# WCRL_Board_V3.net
KiCad netlist of a schematic drawn in EAGLE
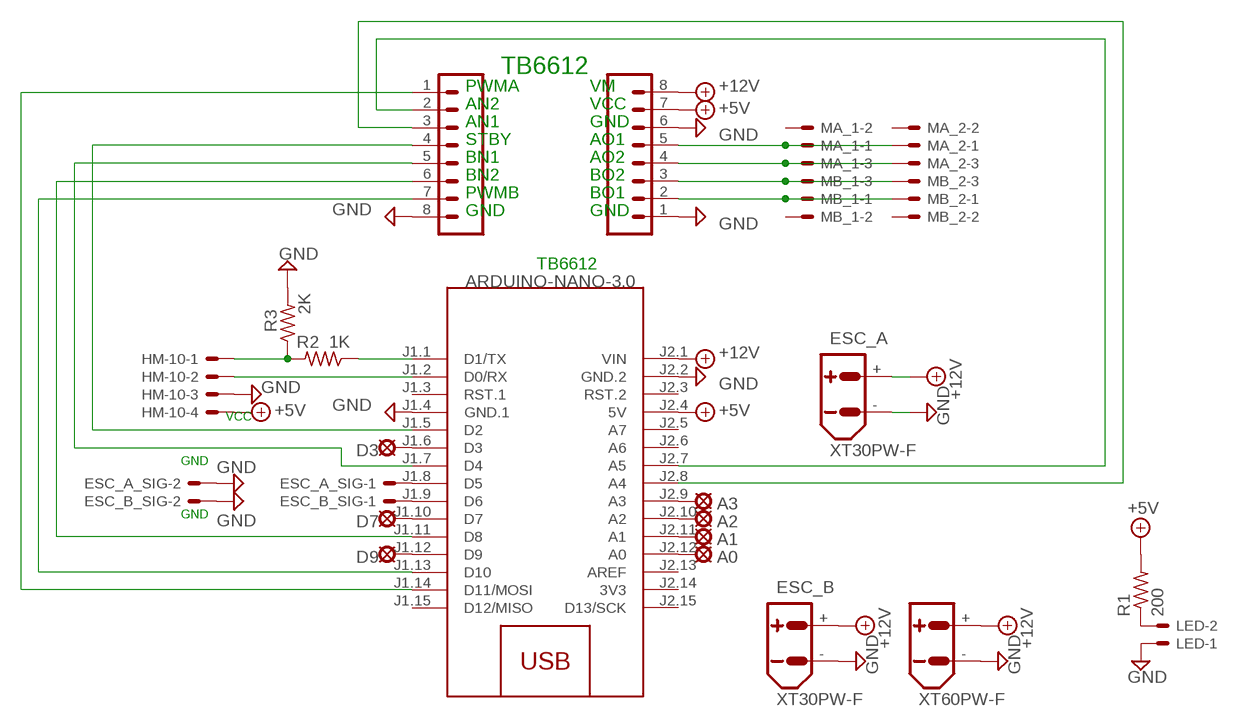
[diagram p0: schematic, sheet 1]

(export (version "E")
  (design (tool "Eeschema 10.0.6"))
  (components
    (comp (ref "A0")
      (value "LSP10")
      (footprint "eagle-import:LSP10")
      (libsource (lib "eagle-import") (part "LSP10"))
    )
    (comp (ref "A1")
      (value "LSP10")
      (footprint "eagle-import:LSP10")
      (libsource (lib "eagle-import") (part "LSP10"))
    )
    (comp (ref "A2")
      (value "LSP10")
      (footprint "eagle-import:LSP10")
      (libsource (lib "eagle-import") (part "LSP10"))
    )
    (comp (ref "A3")
      (value "LSP10")
      (footprint "eagle-import:LSP10")
      (libsource (lib "eagle-import") (part "LSP10"))
    )
    (comp (ref "BATTERY")
      (value "XT60PW-F")
      (footprint "eagle-import:XT60PW-F")
      (libsource (lib "eagle-import") (part "XT60PW-F"))
    )
    (comp (ref "D3")
      (value "LSP10")
      (footprint "eagle-import:LSP10")
      (libsource (lib "eagle-import") (part "LSP10"))
    )
    (comp (ref "D7")
      (value "LSP10")
      (footprint "eagle-import:LSP10")
      (libsource (lib "eagle-import") (part "LSP10"))
    )
    (comp (ref "D9")
      (value "LSP10")
      (footprint "eagle-import:LSP10")
      (libsource (lib "eagle-import") (part "LSP10"))
    )
    (comp (ref "ESC_A")
      (value "XT30PW-F")
      (footprint "eagle-import:XT30PW-F")
      (libsource (lib "eagle-import") (part "XT30PW-F"))
    )
    (comp (ref "ESC_A_SIG")
      (value "JST-XH-02-PIN-LONG-PAD")
      (footprint "eagle-import:JST-XH-02-PACKAGE-LONG-PAD")
      (libsource (lib "eagle-import") (part "JST-XH-02-PIN-LONG-PAD"))
    )
    (comp (ref "ESC_B")
      (value "XT30PW-F")
      (footprint "eagle-import:XT30PW-F")
      (libsource (lib "eagle-import") (part "XT30PW-F"))
    )
    (comp (ref "ESC_B_SIG")
      (value "JST-XH-02-PIN-LONG-PAD")
      (footprint "eagle-import:JST-XH-02-PACKAGE-LONG-PAD")
      (libsource (lib "eagle-import") (part "JST-XH-02-PIN-LONG-PAD"))
    )
    (comp (ref "HM-10")
      (value "JST-XH-04-PIN-LONG-PAD")
      (footprint "eagle-import:JST-XH-04-PACKAGE-LONG-PAD")
      (libsource (lib "eagle-import") (part "JST-XH-04-PIN-LONG-PAD"))
    )
    (comp (ref "J1")
      (value "CONN_08NO_SILK_FEMALE_PTH")
      (footprint "eagle-import:1X08_NO_SILK")
      (libsource (lib "eagle-import") (part "CONN_08NO_SILK_FEMALE_PTH"))
    )
    (comp (ref "J2")
      (value "CONN_08NO_SILK_FEMALE_PTH")
      (footprint "eagle-import:1X08_NO_SILK")
      (libsource (lib "eagle-import") (part "CONN_08NO_SILK_FEMALE_PTH"))
    )
    (comp (ref "LED")
      (value "JST-XH-02-PIN-LONG-PAD")
      (footprint "eagle-import:JST-XH-02-PACKAGE-LONG-PAD")
      (libsource (lib "eagle-import") (part "JST-XH-02-PIN-LONG-PAD"))
    )
    (comp (ref "M1")
      (value "ARDUINO-NANO-3.0")
      (footprint "eagle-import:ARDUINO-NANO-3.0")
      (libsource (lib "eagle-import") (part "ARDUINO-NANO-3.0"))
    )
    (comp (ref "MA_1")
      (value "JST-XH-03-PIN-LONG-PAD")
      (footprint "eagle-import:JST-XH-03-PACKAGE-LONG-PAD")
      (libsource (lib "eagle-import") (part "JST-XH-03-PIN-LONG-PAD"))
    )
    (comp (ref "MA_2")
      (value "JST-XH-03-PIN-LONG-PAD")
      (footprint "eagle-import:JST-XH-03-PACKAGE-LONG-PAD")
      (libsource (lib "eagle-import") (part "JST-XH-03-PIN-LONG-PAD"))
    )
    (comp (ref "MB_1")
      (value "JST-XH-03-PIN-LONG-PAD")
      (footprint "eagle-import:JST-XH-03-PACKAGE-LONG-PAD")
      (libsource (lib "eagle-import") (part "JST-XH-03-PIN-LONG-PAD"))
    )
    (comp (ref "MB_2")
      (value "JST-XH-03-PIN-LONG-PAD")
      (footprint "eagle-import:JST-XH-03-PACKAGE-LONG-PAD")
      (libsource (lib "eagle-import") (part "JST-XH-03-PIN-LONG-PAD"))
    )
    (comp (ref "R1")
      (value "200")
      (footprint "eagle-import:0204_5")
      (libsource (lib "eagle-import") (part "R-US_0204/5"))
    )
    (comp (ref "R2")
      (value "1K")
      (footprint "eagle-import:0204_5")
      (libsource (lib "eagle-import") (part "R-US_0204/5"))
    )
    (comp (ref "R3")
      (value "2K")
      (footprint "eagle-import:0204_5")
      (libsource (lib "eagle-import") (part "R-US_0204/5"))
    )
  )
  (nets
    (net (code "1") (name "+5V") (class "Default")
      (node (ref "HM-10") (pin "4") (pinfunction "S_4") (pintype "passive"))
      (node (ref "J1") (pin "7") (pinfunction "7_7") (pintype "passive"))
      (node (ref "M1") (pin "J2.4") (pinfunction "5V_J2.4") (pintype "power_in"))
      (node (ref "R1") (pin "2") (pinfunction "2_2") (pintype "passive"))
    )
    (net (code "2") (name "+12V") (class "Default")
      (node (ref "BATTERY") (pin "+") (pinfunction "+_+") (pintype "power_in"))
      (node (ref "ESC_A") (pin "+") (pinfunction "+_+") (pintype "power_in"))
      (node (ref "ESC_B") (pin "+") (pinfunction "+_+") (pintype "power_in"))
      (node (ref "J1") (pin "8") (pinfunction "8_8") (pintype "passive"))
      (node (ref "M1") (pin "J2.1") (pinfunction "VIN_J2.1") (pintype "power_in"))
    )
    (net (code "3") (name "/3V3") (class "Default")
      (node (ref "M1") (pin "J2.14") (pinfunction "3V3_J2.14") (pintype "power_in"))
    )
    (net (code "4") (name "GND") (class "Default")
      (node (ref "BATTERY") (pin "-") (pinfunction "-_-") (pintype "power_in"))
      (node (ref "ESC_A") (pin "-") (pinfunction "-_-") (pintype "power_in"))
      (node (ref "ESC_A_SIG") (pin "2") (pinfunction "S_2") (pintype "passive"))
      (node (ref "ESC_B") (pin "-") (pinfunction "-_-") (pintype "power_in"))
      (node (ref "ESC_B_SIG") (pin "2") (pinfunction "S_2") (pintype "passive"))
      (node (ref "HM-10") (pin "3") (pinfunction "S_3") (pintype "passive"))
      (node (ref "J1") (pin "1") (pinfunction "1_1") (pintype "passive"))
      (node (ref "J1") (pin "6") (pinfunction "6_6") (pintype "passive"))
      (node (ref "J2") (pin "8") (pinfunction "8_8") (pintype "passive"))
      (node (ref "LED") (pin "1") (pinfunction "S_1") (pintype "passive"))
      (node (ref "M1") (pin "J1.4") (pinfunction "GND.1_J1.4") (pintype "power_in"))
      (node (ref "M1") (pin "J2.2") (pinfunction "GND.2_J2.2") (pintype "power_in"))
      (node (ref "R3") (pin "2") (pinfunction "2_2") (pintype "passive"))
    )
    (net (code "5") (name "Net-(ESC_A_SIGA-S)") (class "Default")
      (node (ref "ESC_A_SIG") (pin "1") (pinfunction "S_1") (pintype "passive"))
      (node (ref "M1") (pin "J1.8") (pinfunction "D5_J1.8") (pintype "bidirectional"))
    )
    (net (code "6") (name "Net-(ESC_B_SIGA-S)") (class "Default")
      (node (ref "ESC_B_SIG") (pin "1") (pinfunction "S_1") (pintype "passive"))
      (node (ref "M1") (pin "J1.9") (pinfunction "D6_J1.9") (pintype "bidirectional"))
    )
    (net (code "7") (name "Net-(HM-10A-S)") (class "Default")
      (node (ref "HM-10") (pin "1") (pinfunction "S_1") (pintype "passive"))
      (node (ref "R2") (pin "2") (pinfunction "2_2") (pintype "passive"))
      (node (ref "R3") (pin "1") (pinfunction "1_1") (pintype "passive"))
    )
    (net (code "8") (name "Net-(HM-10B-S)") (class "Default")
      (node (ref "HM-10") (pin "2") (pinfunction "S_2") (pintype "passive"))
      (node (ref "M1") (pin "J1.2") (pinfunction "D0/RX_J1.2") (pintype "bidirectional"))
    )
    (net (code "9") (name "Net-(LEDB-S)") (class "Default")
      (node (ref "LED") (pin "2") (pinfunction "S_2") (pintype "passive"))
      (node (ref "R1") (pin "1") (pinfunction "1_1") (pintype "passive"))
    )
    (net (code "10") (name "Net-(M1-A0)") (class "Default")
      (node (ref "A0") (pin "MP") (pinfunction "MP_MP") (pintype "passive"))
      (node (ref "M1") (pin "J2.12") (pinfunction "A0_J2.12") (pintype "bidirectional"))
    )
    (net (code "11") (name "Net-(M1-A1)") (class "Default")
      (node (ref "A1") (pin "MP") (pinfunction "MP_MP") (pintype "passive"))
      (node (ref "M1") (pin "J2.11") (pinfunction "A1_J2.11") (pintype "bidirectional"))
    )
    (net (code "12") (name "Net-(M1-A2)") (class "Default")
      (node (ref "A2") (pin "MP") (pinfunction "MP_MP") (pintype "passive"))
      (node (ref "M1") (pin "J2.10") (pinfunction "A2_J2.10") (pintype "bidirectional"))
    )
    (net (code "13") (name "Net-(M1-A3)") (class "Default")
      (node (ref "A3") (pin "MP") (pinfunction "MP_MP") (pintype "passive"))
      (node (ref "M1") (pin "J2.9") (pinfunction "A3_J2.9") (pintype "bidirectional"))
    )
    (net (code "14") (name "Net-(M1-A4)") (class "Default")
      (node (ref "J2") (pin "3") (pinfunction "3_3") (pintype "passive"))
      (node (ref "M1") (pin "J2.8") (pinfunction "A4_J2.8") (pintype "bidirectional"))
    )
    (net (code "15") (name "Net-(M1-A5)") (class "Default")
      (node (ref "J2") (pin "2") (pinfunction "2_2") (pintype "passive"))
      (node (ref "M1") (pin "J2.7") (pinfunction "A5_J2.7") (pintype "bidirectional"))
    )
    (net (code "16") (name "Net-(M1-D1{slash}TX)") (class "Default")
      (node (ref "M1") (pin "J1.1") (pinfunction "D1/TX_J1.1") (pintype "bidirectional"))
      (node (ref "R2") (pin "1") (pinfunction "1_1") (pintype "passive"))
    )
    (net (code "17") (name "Net-(M1-D2)") (class "Default")
      (node (ref "J2") (pin "4") (pinfunction "4_4") (pintype "passive"))
      (node (ref "M1") (pin "J1.5") (pinfunction "D2_J1.5") (pintype "bidirectional"))
    )
    (net (code "18") (name "Net-(M1-D3)") (class "Default")
      (node (ref "D3") (pin "MP") (pinfunction "MP_MP") (pintype "passive"))
      (node (ref "M1") (pin "J1.6") (pinfunction "D3_J1.6") (pintype "bidirectional"))
    )
    (net (code "19") (name "Net-(M1-D4)") (class "Default")
      (node (ref "J2") (pin "5") (pinfunction "5_5") (pintype "passive"))
      (node (ref "M1") (pin "J1.7") (pinfunction "D4_J1.7") (pintype "bidirectional"))
    )
    (net (code "20") (name "Net-(M1-D7)") (class "Default")
      (node (ref "D7") (pin "MP") (pinfunction "MP_MP") (pintype "passive"))
      (node (ref "M1") (pin "J1.10") (pinfunction "D7_J1.10") (pintype "bidirectional"))
    )
    (net (code "21") (name "Net-(M1-D8)") (class "Default")
      (node (ref "J2") (pin "6") (pinfunction "6_6") (pintype "passive"))
      (node (ref "M1") (pin "J1.11") (pinfunction "D8_J1.11") (pintype "bidirectional"))
    )
    (net (code "22") (name "Net-(M1-D9)") (class "Default")
      (node (ref "D9") (pin "MP") (pinfunction "MP_MP") (pintype "passive"))
      (node (ref "M1") (pin "J1.12") (pinfunction "D9_J1.12") (pintype "bidirectional"))
    )
    (net (code "23") (name "Net-(M1-D10)") (class "Default")
      (node (ref "J2") (pin "7") (pinfunction "7_7") (pintype "passive"))
      (node (ref "M1") (pin "J1.13") (pinfunction "D10_J1.13") (pintype "bidirectional"))
    )
    (net (code "24") (name "Net-(M1-D11{slash}MOSI)") (class "Default")
      (node (ref "J2") (pin "1") (pinfunction "1_1") (pintype "passive"))
      (node (ref "M1") (pin "J1.14") (pinfunction "D11/MOSI_J1.14") (pintype "bidirectional"))
    )
    (net (code "25") (name "Net-(MA_1A-S)") (class "Default")
      (node (ref "J1") (pin "5") (pinfunction "5_5") (pintype "passive"))
      (node (ref "MA_1") (pin "1") (pinfunction "S_1") (pintype "passive"))
      (node (ref "MA_2") (pin "1") (pinfunction "S_1") (pintype "passive"))
    )
    (net (code "26") (name "Net-(MA_1C-S)") (class "Default")
      (node (ref "J1") (pin "4") (pinfunction "4_4") (pintype "passive"))
      (node (ref "MA_1") (pin "3") (pinfunction "S_3") (pintype "passive"))
      (node (ref "MA_2") (pin "3") (pinfunction "S_3") (pintype "passive"))
    )
    (net (code "27") (name "Net-(MB_1A-S)") (class "Default")
      (node (ref "J1") (pin "2") (pinfunction "2_2") (pintype "passive"))
      (node (ref "MB_1") (pin "1") (pinfunction "S_1") (pintype "passive"))
      (node (ref "MB_2") (pin "1") (pinfunction "S_1") (pintype "passive"))
    )
    (net (code "28") (name "Net-(MB_1C-S)") (class "Default")
      (node (ref "J1") (pin "3") (pinfunction "3_3") (pintype "passive"))
      (node (ref "MB_1") (pin "3") (pinfunction "S_3") (pintype "passive"))
      (node (ref "MB_2") (pin "3") (pinfunction "S_3") (pintype "passive"))
    )
    (net (code "29") (name "unconnected-(M1-A6-PadJ2.6)") (class "Default")
      (node (ref "M1") (pin "J2.6") (pinfunction "A6_J2.6") (pintype "bidirectional"))
    )
    (net (code "30") (name "unconnected-(M1-A7-PadJ2.5)") (class "Default")
      (node (ref "M1") (pin "J2.5") (pinfunction "A7_J2.5") (pintype "bidirectional"))
    )
    (net (code "31") (name "unconnected-(M1-AREF-PadJ2.13)") (class "Default")
      (node (ref "M1") (pin "J2.13") (pinfunction "AREF_J2.13") (pintype "bidirectional"))
    )
    (net (code "32") (name "unconnected-(M1-D12{slash}MISO-PadJ1.15)") (class "Default")
      (node (ref "M1") (pin "J1.15") (pinfunction "D12/MISO_J1.15") (pintype "bidirectional"))
    )
    (net (code "33") (name "unconnected-(M1-D13{slash}SCK-PadJ2.15)") (class "Default")
      (node (ref "M1") (pin "J2.15") (pinfunction "D13/SCK_J2.15") (pintype "bidirectional"))
    )
    (net (code "34") (name "unconnected-(M1-RST.1-PadJ1.3)") (class "Default")
      (node (ref "M1") (pin "J1.3") (pinfunction "RST.1_J1.3") (pintype "bidirectional"))
    )
    (net (code "35") (name "unconnected-(M1-RST.2-PadJ2.3)") (class "Default")
      (node (ref "M1") (pin "J2.3") (pinfunction "RST.2_J2.3") (pintype "bidirectional"))
    )
    (net (code "36") (name "unconnected-(MA_1B-S-Pad2)") (class "Default")
      (node (ref "MA_1") (pin "2") (pinfunction "S_2") (pintype "passive"))
    )
    (net (code "37") (name "unconnected-(MA_2B-S-Pad2)") (class "Default")
      (node (ref "MA_2") (pin "2") (pinfunction "S_2") (pintype "passive"))
    )
    (net (code "38") (name "unconnected-(MB_1B-S-Pad2)") (class "Default")
      (node (ref "MB_1") (pin "2") (pinfunction "S_2") (pintype "passive"))
    )
    (net (code "39") (name "unconnected-(MB_2B-S-Pad2)") (class "Default")
      (node (ref "MB_2") (pin "2") (pinfunction "S_2") (pintype "passive"))
    )
  )
)
